# sematik_mos.net
KiCad netlist of a schematic drawn in Altium Designer
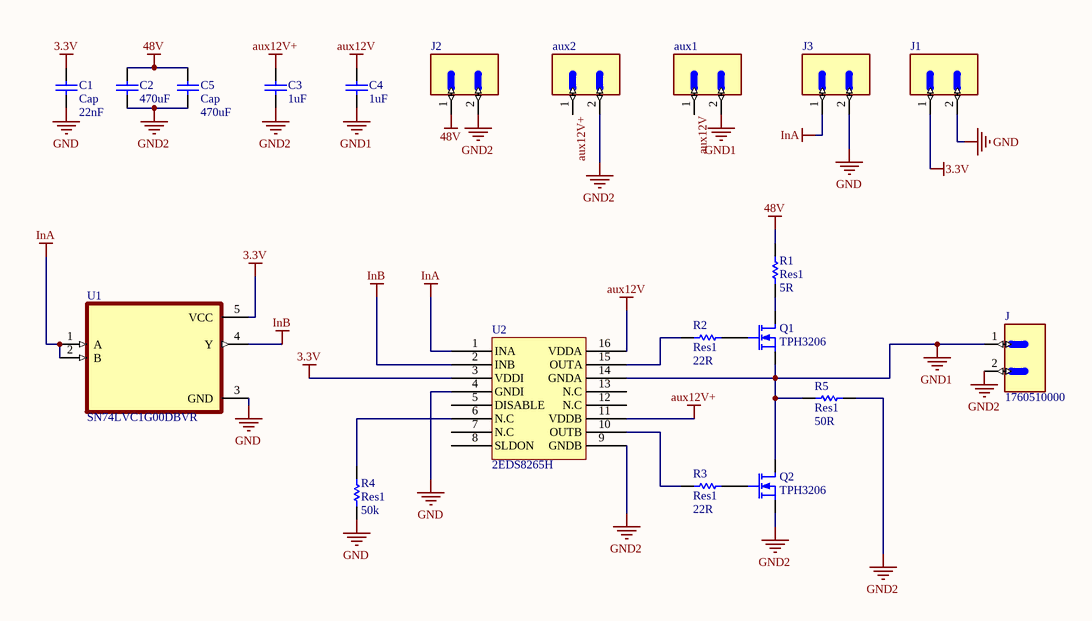
[diagram p0: sematik_mos.SchDoc]

(export (version "E")
  (design (tool "Eeschema 10.0.6"))
  (components
    (comp (ref "aux1")
      (value "1760510000")
      (footprint "1760490000")
      (description "2 Position Wire to Board Terminal Block Horizontal with Board 0.200 _5.08mm_ Through Hole")
      (fields (field (name "MF") "Weidmuller"))
      (libsource (lib "1760510000") (part "1760510000"))
    )
    (comp (ref "aux2")
      (value "1760510000")
      (footprint "1760490000")
      (description "2 Position Wire to Board Terminal Block Horizontal with Board 0.200 _5.08mm_ Through Hole")
      (fields (field (name "MF") "Weidmuller"))
      (libsource (lib "1760510000") (part "1760510000"))
    )
    (comp (ref "C1")
      (value "Cap")
      (footprint "RAD-0.3")
      (description "Capacitor")
      (fields (field (name "ALTIUM_VALUE") "22nF") (field (name "PUBLISHER") "Altium Limited"))
      (libsource (lib "Miscellaneous Devices") (part "Cap"))
    )
    (comp (ref "C2")
      (value "470uF")
      (footprint "RAD-0.3")
      (description "Capacitor")
      (fields (field (name "PUBLISHER") "Altium Limited"))
      (libsource (lib "Miscellaneous Devices") (part "Cap"))
    )
    (comp (ref "C3")
      (value "1uF")
      (footprint "RAD-0.3")
      (description "Capacitor")
      (fields (field (name "PUBLISHER") "Altium Limited"))
      (libsource (lib "Miscellaneous Devices") (part "Cap"))
    )
    (comp (ref "C4")
      (value "1uF")
      (footprint "RAD-0.3")
      (description "Capacitor")
      (fields (field (name "PUBLISHER") "Altium Limited"))
      (libsource (lib "Miscellaneous Devices") (part "Cap"))
    )
    (comp (ref "C5")
      (value "Cap")
      (footprint "RAD-0.3")
      (description "Capacitor")
      (fields (field (name "ALTIUM_VALUE") "470uF") (field (name "PUBLISHER") "Altium Limited"))
      (libsource (lib "Miscellaneous Devices") (part "Cap"))
    )
    (comp (ref "J")
      (value "1760510000")
      (footprint "1760490000")
      (description "2 Position Wire to Board Terminal Block Horizontal with Board 0.200 _5.08mm_ Through Hole")
      (fields (field (name "MF") "Weidmuller"))
      (libsource (lib "") (part "1760510000_1"))
    )
    (comp (ref "J1")
      (value "1760510000")
      (footprint "1760490000")
      (description "2 Position Wire to Board Terminal Block Horizontal with Board 0.200 _5.08mm_ Through Hole")
      (fields (field (name "MF") "Weidmuller"))
      (libsource (lib "1760510000") (part "1760510000"))
    )
    (comp (ref "J2")
      (value "1760510000")
      (footprint "1760490000")
      (description "2 Position Wire to Board Terminal Block Horizontal with Board 0.200 _5.08mm_ Through Hole")
      (fields (field (name "MF") "Weidmuller"))
      (libsource (lib "1760510000") (part "1760510000"))
    )
    (comp (ref "J3")
      (value "1760510000")
      (footprint "1760490000")
      (description "2 Position Wire to Board Terminal Block Horizontal with Board 0.200 _5.08mm_ Through Hole")
      (fields (field (name "MF") "Weidmuller"))
      (libsource (lib "1760510000") (part "1760510000"))
    )
    (comp (ref "Q1")
      (value "TPH3206")
      (footprint "tph3206_powmos")
      (libsource (lib "mosfet_tph3206") (part "mosfetss"))
    )
    (comp (ref "Q2")
      (value "TPH3206")
      (footprint "tph3206_powmos")
      (libsource (lib "mosfet_tph3206") (part "mosfetss"))
    )
    (comp (ref "R1")
      (value "Res1")
      (footprint "AXIAL-0.3")
      (description "Resistor")
      (fields (field (name "ALTIUM_VALUE") "5R") (field (name "PUBLISHER") "Altium Limited"))
      (libsource (lib "Miscellaneous Devices") (part "Res1"))
    )
    (comp (ref "R2")
      (value "Res1")
      (footprint "AXIAL-0.3")
      (description "Resistor")
      (fields (field (name "ALTIUM_VALUE") "22R") (field (name "PUBLISHER") "Altium Limited"))
      (libsource (lib "Miscellaneous Devices") (part "Res1"))
    )
    (comp (ref "R3")
      (value "Res1")
      (footprint "AXIAL-0.3")
      (description "Resistor")
      (fields (field (name "ALTIUM_VALUE") "22R") (field (name "PUBLISHER") "Altium Limited"))
      (libsource (lib "Miscellaneous Devices") (part "Res1"))
    )
    (comp (ref "R4")
      (value "Res1")
      (footprint "AXIAL-0.3")
      (description "Resistor")
      (fields (field (name "ALTIUM_VALUE") "50k") (field (name "PUBLISHER") "Altium Limited"))
      (libsource (lib "Miscellaneous Devices") (part "Res1"))
    )
    (comp (ref "R5")
      (value "Res1")
      (footprint "AXIAL-0.3")
      (description "Resistor")
      (fields (field (name "ALTIUM_VALUE") "50R") (field (name "PUBLISHER") "Altium Limited"))
      (libsource (lib "Miscellaneous Devices") (part "Res1"))
    )
    (comp (ref "U1")
      (value "SN74LVC1G00DBVR")
      (footprint "SOT95P280X145-5N")
      (description "Single 2 Input Positive NAND Gate 5-SOT-23 -40 to 125")
      (fields
        (field (name "MF") "Texas Instruments")
        (field (name "BUYPART") "https://www.snapeda.com/parts/SN74LVC1G00DBVR/Texas%20Instruments/view-part/410267/?ref=eda")
      )
      (libsource (lib "SN74LVC1G00DBVR") (part "SN74LVC1G00DBVR"))
    )
    (comp (ref "U2")
      (value "2EDS8265H")
      (footprint "2eds8265h_pcb")
      (description "DSO-16 socket surface mount")
      (libsource (lib "Schlib1") (part "Component_1"))
    )
  )
  (nets
    (net (code "1") (name "3.3V") (class "Default")
      (node (ref "C1") (pin "2") (pinfunction "2_2") (pintype "passive"))
      (node (ref "J1") (pin "1") (pinfunction "1_1") (pintype "bidirectional"))
      (node (ref "U1") (pin "5") (pinfunction "VCC_5") (pintype "power_in"))
      (node (ref "U2") (pin "3") (pinfunction "VDDI_3") (pintype "passive"))
    )
    (net (code "2") (name "48V") (class "Default")
      (node (ref "C2") (pin "2") (pinfunction "2_2") (pintype "passive"))
      (node (ref "C5") (pin "2") (pinfunction "2_2") (pintype "passive"))
      (node (ref "J2") (pin "1") (pinfunction "1_1") (pintype "bidirectional"))
      (node (ref "R1") (pin "2") (pinfunction "2_2") (pintype "passive"))
    )
    (net (code "3") (name "GND") (class "Default")
      (node (ref "C1") (pin "1") (pinfunction "1_1") (pintype "passive"))
      (node (ref "J1") (pin "2") (pinfunction "2_2") (pintype "bidirectional"))
      (node (ref "J3") (pin "2") (pinfunction "2_2") (pintype "bidirectional"))
      (node (ref "R4") (pin "1") (pinfunction "1_1") (pintype "passive"))
      (node (ref "U1") (pin "3") (pinfunction "GND_3") (pintype "power_in"))
      (node (ref "U2") (pin "4") (pinfunction "GNDI_4") (pintype "passive"))
    )
    (net (code "4") (name "GND1") (class "Default")
      (node (ref "C4") (pin "1") (pinfunction "1_1") (pintype "passive"))
      (node (ref "J") (pin "1") (pinfunction "1_1") (pintype "bidirectional"))
      (node (ref "Q1") (pin "2") (pinfunction "S_2") (pintype "passive"))
      (node (ref "Q2") (pin "3") (pinfunction "D_3") (pintype "passive"))
      (node (ref "R5") (pin "2") (pinfunction "2_2") (pintype "passive"))
      (node (ref "U2") (pin "14") (pinfunction "GNDA_14") (pintype "passive"))
      (node (ref "aux1") (pin "2") (pinfunction "2_2") (pintype "bidirectional"))
    )
    (net (code "5") (name "GND2") (class "Default")
      (node (ref "C2") (pin "1") (pinfunction "1_1") (pintype "passive"))
      (node (ref "C3") (pin "1") (pinfunction "1_1") (pintype "passive"))
      (node (ref "C5") (pin "1") (pinfunction "1_1") (pintype "passive"))
      (node (ref "J") (pin "2") (pinfunction "2_2") (pintype "bidirectional"))
      (node (ref "J2") (pin "2") (pinfunction "2_2") (pintype "bidirectional"))
      (node (ref "Q2") (pin "2") (pinfunction "S_2") (pintype "passive"))
      (node (ref "R5") (pin "1") (pinfunction "1_1") (pintype "passive"))
      (node (ref "U2") (pin "9") (pinfunction "GNDB_9") (pintype "passive"))
      (node (ref "aux2") (pin "2") (pinfunction "2_2") (pintype "bidirectional"))
    )
    (net (code "6") (name "InA") (class "Default")
      (node (ref "J3") (pin "1") (pinfunction "1_1") (pintype "bidirectional"))
      (node (ref "U1") (pin "1") (pinfunction "A_1") (pintype "input"))
      (node (ref "U1") (pin "2") (pinfunction "B_2") (pintype "input"))
      (node (ref "U2") (pin "1") (pinfunction "INA_1") (pintype "passive"))
    )
    (net (code "7") (name "InB") (class "Default")
      (node (ref "U1") (pin "4") (pinfunction "Y_4") (pintype "output"))
      (node (ref "U2") (pin "2") (pinfunction "INB_2") (pintype "passive"))
    )
    (net (code "8") (name "Net-(Q1-D)") (class "Default")
      (node (ref "Q1") (pin "3") (pinfunction "D_3") (pintype "passive"))
      (node (ref "R1") (pin "1") (pinfunction "1_1") (pintype "passive"))
    )
    (net (code "9") (name "Net-(Q1-G)") (class "Default")
      (node (ref "Q1") (pin "1") (pinfunction "G_1") (pintype "passive"))
      (node (ref "R2") (pin "1") (pinfunction "1_1") (pintype "passive"))
    )
    (net (code "10") (name "Net-(Q2-G)") (class "Default")
      (node (ref "Q2") (pin "1") (pinfunction "G_1") (pintype "passive"))
      (node (ref "R3") (pin "1") (pinfunction "1_1") (pintype "passive"))
    )
    (net (code "11") (name "Net-(R4-Pad2)") (class "Default")
      (node (ref "R4") (pin "2") (pinfunction "2_2") (pintype "passive"))
      (node (ref "U2") (pin "6") (pinfunction "N.C_6") (pintype "passive"))
    )
    (net (code "12") (name "Net-(U2-OUTA)") (class "Default")
      (node (ref "R2") (pin "2") (pinfunction "2_2") (pintype "passive"))
      (node (ref "U2") (pin "15") (pinfunction "OUTA_15") (pintype "passive"))
    )
    (net (code "13") (name "Net-(U2-OUTB)") (class "Default")
      (node (ref "R3") (pin "2") (pinfunction "2_2") (pintype "passive"))
      (node (ref "U2") (pin "10") (pinfunction "OUTB_10") (pintype "passive"))
    )
    (net (code "14") (name "aux12V") (class "Default")
      (node (ref "C4") (pin "2") (pinfunction "2_2") (pintype "passive"))
      (node (ref "U2") (pin "16") (pinfunction "VDDA_16") (pintype "passive"))
      (node (ref "aux1") (pin "1") (pinfunction "1_1") (pintype "bidirectional"))
    )
    (net (code "15") (name "aux12V+") (class "Default")
      (node (ref "C3") (pin "2") (pinfunction "2_2") (pintype "passive"))
      (node (ref "U2") (pin "11") (pinfunction "VDDB_11") (pintype "passive"))
      (node (ref "aux2") (pin "1") (pinfunction "1_1") (pintype "bidirectional"))
    )
    (net (code "16") (name "unconnected-(U2-DISABLE-Pad5)") (class "Default")
      (node (ref "U2") (pin "5") (pinfunction "DISABLE_5") (pintype "passive"))
    )
    (net (code "17") (name "unconnected-(U2-N.C-Pad7)") (class "Default")
      (node (ref "U2") (pin "7") (pinfunction "N.C_7") (pintype "passive"))
    )
    (net (code "18") (name "unconnected-(U2-N.C-Pad12)") (class "Default")
      (node (ref "U2") (pin "12") (pinfunction "N.C_12") (pintype "passive"))
    )
    (net (code "19") (name "unconnected-(U2-N.C-Pad13)") (class "Default")
      (node (ref "U2") (pin "13") (pinfunction "N.C_13") (pintype "passive"))
    )
    (net (code "20") (name "unconnected-(U2-SLDON-Pad8)") (class "Default")
      (node (ref "U2") (pin "8") (pinfunction "SLDON_8") (pintype "passive"))
    )
  )
)
